# darkgame-motor.net
KiCad netlist of a schematic drawn in EAGLE
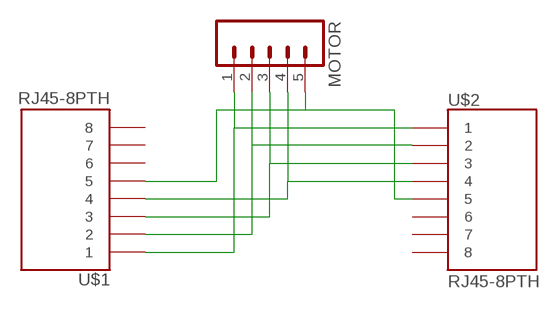
[diagram p0: schematic, sheet 1]

(export (version "E")
  (design (tool "Eeschema 10.0.6"))
  (components
    (comp (ref "MOTOR")
      (value "M05PTH")
      (footprint "eagle-import:1X05")
      (libsource (lib "eagle-import") (part "M05PTH"))
    )
    (comp (ref "U$1")
      (value "RJ45-8PTH")
      (footprint "eagle-import:RJ45-8")
      (libsource (lib "eagle-import") (part "RJ45-8PTH"))
    )
    (comp (ref "U$2")
      (value "RJ45-8PTH")
      (footprint "eagle-import:RJ45-8")
      (libsource (lib "eagle-import") (part "RJ45-8PTH"))
    )
  )
  (nets
    (net (code "1") (name "Net-(MOTOR-Pad1)") (class "Default")
      (node (ref "MOTOR") (pin "1") (pinfunction "1_1") (pintype "passive"))
      (node (ref "U$1") (pin "1") (pinfunction "1_1") (pintype "bidirectional"))
      (node (ref "U$2") (pin "1") (pinfunction "1_1") (pintype "bidirectional"))
    )
    (net (code "2") (name "Net-(MOTOR-Pad2)") (class "Default")
      (node (ref "MOTOR") (pin "2") (pinfunction "2_2") (pintype "passive"))
      (node (ref "U$1") (pin "2") (pinfunction "2_2") (pintype "bidirectional"))
      (node (ref "U$2") (pin "2") (pinfunction "2_2") (pintype "bidirectional"))
    )
    (net (code "3") (name "Net-(MOTOR-Pad3)") (class "Default")
      (node (ref "MOTOR") (pin "3") (pinfunction "3_3") (pintype "passive"))
      (node (ref "U$1") (pin "3") (pinfunction "3_3") (pintype "bidirectional"))
      (node (ref "U$2") (pin "3") (pinfunction "3_3") (pintype "bidirectional"))
    )
    (net (code "4") (name "Net-(MOTOR-Pad4)") (class "Default")
      (node (ref "MOTOR") (pin "4") (pinfunction "4_4") (pintype "passive"))
      (node (ref "U$1") (pin "4") (pinfunction "4_4") (pintype "bidirectional"))
      (node (ref "U$2") (pin "4") (pinfunction "4_4") (pintype "bidirectional"))
    )
    (net (code "5") (name "Net-(MOTOR-Pad5)") (class "Default")
      (node (ref "MOTOR") (pin "5") (pinfunction "5_5") (pintype "passive"))
      (node (ref "U$1") (pin "5") (pinfunction "5_5") (pintype "bidirectional"))
      (node (ref "U$2") (pin "5") (pinfunction "5_5") (pintype "bidirectional"))
    )
    (net (code "6") (name "unconnected-(U$1-Pad6)") (class "Default")
      (node (ref "U$1") (pin "6") (pinfunction "6_6") (pintype "bidirectional"))
    )
    (net (code "7") (name "unconnected-(U$1-Pad7)") (class "Default")
      (node (ref "U$1") (pin "7") (pinfunction "7_7") (pintype "bidirectional"))
    )
    (net (code "8") (name "unconnected-(U$1-Pad8)") (class "Default")
      (node (ref "U$1") (pin "8") (pinfunction "8_8") (pintype "bidirectional"))
    )
    (net (code "9") (name "unconnected-(U$2-Pad6)") (class "Default")
      (node (ref "U$2") (pin "6") (pinfunction "6_6") (pintype "bidirectional"))
    )
    (net (code "10") (name "unconnected-(U$2-Pad7)") (class "Default")
      (node (ref "U$2") (pin "7") (pinfunction "7_7") (pintype "bidirectional"))
    )
    (net (code "11") (name "unconnected-(U$2-Pad8)") (class "Default")
      (node (ref "U$2") (pin "8") (pinfunction "8_8") (pintype "bidirectional"))
    )
  )
)
